# PWR.net
KiCad netlist of a schematic drawn in Altium Designer
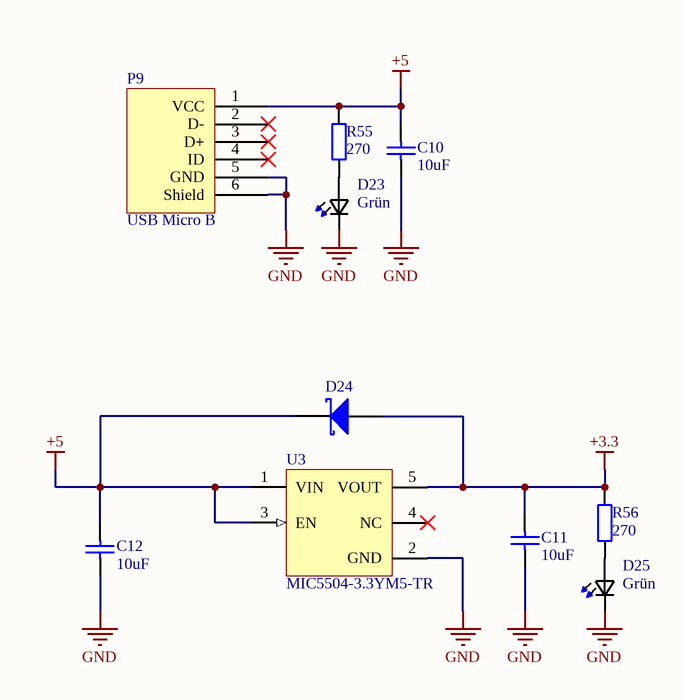
[diagram p0: PWR.SchDoc]

(export (version "E")
  (design (tool "Eeschema 10.0.6"))
  (components
    (comp (ref "C10")
      (value "10uF")
      (footprint "CAP_0805i_2012m -N")
      (description "capacitor")
      (libsource (lib "IDSC std generic parts") (part "Cap"))
    )
    (comp (ref "C11")
      (value "10uF")
      (footprint "CAP_0805i_2012m -N")
      (description "capacitor")
      (libsource (lib "IDSC std generic parts") (part "Cap"))
    )
    (comp (ref "C12")
      (value "10uF")
      (footprint "CAP_0805i_2012m -N")
      (description "capacitor")
      (libsource (lib "IDSC std generic parts") (part "Cap"))
    )
    (comp (ref "D23")
      (value "Grün")
      (footprint "*0603")
      (description "LED; SMD; 0603; gr黱; 35mcd; 1.6x0.8x0.55mm; 130掳; 2梅2.V; 20mA")
      (fields (field (name "MP") "LTST-C191KGKT") (field (name "DIGI-KEY_PART_NUMBER") "160-1446-1-ND"))
      (libsource (lib "Funk") (part "LTST-C191KGKT"))
    )
    (comp (ref "D24")
      (value "Diode  Schottky")
      (footprint "SOD123")
      (description "Schottky Diode")
      (libsource (lib "IDSC std generic parts") (part "Diode  Schottky"))
    )
    (comp (ref "D25")
      (value "Grün")
      (footprint "*0603")
      (description "LED; SMD; 0603; gr黱; 35mcd; 1.6x0.8x0.55mm; 130掳; 2梅2.V; 20mA")
      (fields (field (name "MP") "LTST-C191KGKT") (field (name "DIGI-KEY_PART_NUMBER") "160-1446-1-ND"))
      (libsource (lib "Funk") (part "LTST-C191KGKT"))
    )
    (comp (ref "P9")
      (value "USB Micro B")
      (footprint "MCR-B-S-RA-SMT-EH4B-T/R")
      (libsource (lib "LIB") (part "USB Mikro B"))
    )
    (comp (ref "R55")
      (value "270")
      (footprint "RES_0603i_1608m -N")
      (description "Resistor")
      (libsource (lib "IDSC std generic parts") (part "Res"))
    )
    (comp (ref "R56")
      (value "270")
      (footprint "RES_0603i_1608m -N")
      (description "Resistor")
      (libsource (lib "IDSC std generic parts") (part "Res"))
    )
    (comp (ref "U3")
      (value "MIC5504-3.3YM5-TR")
      (footprint "MCHP-SOT-23-M5_V")
      (fields (field (name "MANUFACTURER") "Microchip"))
      (libsource (lib "Altium Content Vault") (part "MCHP-MIC5504-SOT-23-M5"))
    )
  )
  (nets
    (net (code "1") (name "+3.3") (class "Default")
      (node (ref "C11") (pin "2") (pinfunction "2_2") (pintype "passive"))
      (node (ref "D24") (pin "1") (pinfunction "A_1") (pintype "passive"))
      (node (ref "R56") (pin "2") (pinfunction "2_2") (pintype "passive"))
      (node (ref "U3") (pin "5") (pinfunction "VOUT_5") (pintype "power_in"))
    )
    (net (code "2") (name "+5") (class "Default")
      (node (ref "C10") (pin "2") (pinfunction "2_2") (pintype "passive"))
      (node (ref "C12") (pin "2") (pinfunction "2_2") (pintype "passive"))
      (node (ref "D24") (pin "2") (pinfunction "K_2") (pintype "passive"))
      (node (ref "P9") (pin "1") (pinfunction "VCC_1") (pintype "passive"))
      (node (ref "R55") (pin "2") (pinfunction "2_2") (pintype "passive"))
      (node (ref "U3") (pin "1") (pinfunction "VIN_1") (pintype "power_in"))
      (node (ref "U3") (pin "3") (pinfunction "EN_3") (pintype "input"))
    )
    (net (code "3") (name "GND") (class "Default")
      (node (ref "C10") (pin "1") (pinfunction "1_1") (pintype "passive"))
      (node (ref "C11") (pin "1") (pinfunction "1_1") (pintype "passive"))
      (node (ref "C12") (pin "1") (pinfunction "1_1") (pintype "passive"))
      (node (ref "D23") (pin "1") (pinfunction "K2_1") (pintype "passive"))
      (node (ref "D25") (pin "1") (pinfunction "K2_1") (pintype "passive"))
      (node (ref "P9") (pin "5") (pinfunction "GND_5") (pintype "passive"))
      (node (ref "P9") (pin "6") (pinfunction "Shield_6") (pintype "passive"))
      (node (ref "U3") (pin "2") (pinfunction "GND_2") (pintype "power_in"))
    )
    (net (code "4") (name "Net-(D23-A2)") (class "Default")
      (node (ref "D23") (pin "2") (pinfunction "A2_2") (pintype "passive"))
      (node (ref "R55") (pin "1") (pinfunction "1_1") (pintype "passive"))
    )
    (net (code "5") (name "Net-(D25-A2)") (class "Default")
      (node (ref "D25") (pin "2") (pinfunction "A2_2") (pintype "passive"))
      (node (ref "R56") (pin "1") (pinfunction "1_1") (pintype "passive"))
    )
    (net (code "6") (name "unconnected-(P9-D+-Pad3)") (class "Default")
      (node (ref "P9") (pin "3") (pinfunction "D+_3") (pintype "passive+no_connect"))
    )
    (net (code "7") (name "unconnected-(P9-D--Pad2)") (class "Default")
      (node (ref "P9") (pin "2") (pinfunction "D-_2") (pintype "passive+no_connect"))
    )
    (net (code "8") (name "unconnected-(P9-ID-Pad4)") (class "Default")
      (node (ref "P9") (pin "4") (pinfunction "ID_4") (pintype "passive+no_connect"))
    )
    (net (code "9") (name "unconnected-(U3-NC-Pad4)") (class "Default")
      (node (ref "U3") (pin "4") (pinfunction "NC_4") (pintype "passive+no_connect"))
    )
  )
)
